# COMMUNICATION.net
KiCad netlist of a schematic drawn in Altium Designer
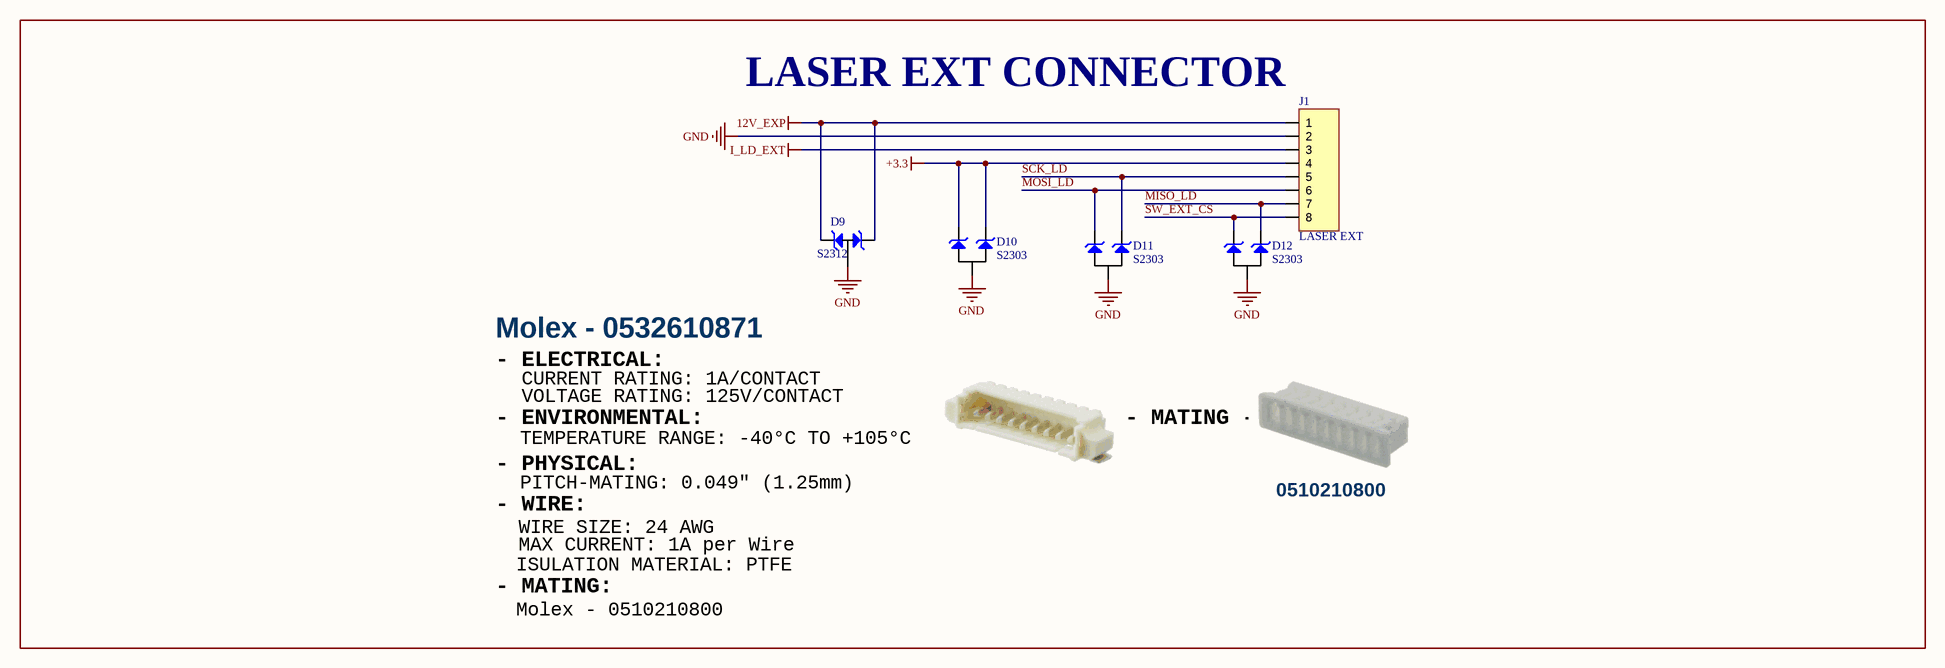
[diagram p0: COMMUNICATION.SchDoc]

(export (version "E")
  (design (tool "Eeschema 10.0.6"))
  (components
    (comp (ref "D9")
      (value "S2312")
      (footprint "SOT23-123")
      (description "TVS DIODE 12VWM 19VC SOT23, P/N:  S2312")
      (libsource (lib "Library") (part "S2315"))
    )
    (comp (ref "D10")
      (value "S2303")
      (footprint "SOT23-123")
      (description "TVS DIODE 3.3VWM 8VC SOT23, P/N:  \r\nS2303")
      (libsource (lib "Library") (part "S2303"))
    )
    (comp (ref "D11")
      (value "S2303")
      (footprint "SOT23-123")
      (description "TVS DIODE 3.3VWM 8VC SOT23, P/N:  \r\nS2303")
      (libsource (lib "Library") (part "S2303"))
    )
    (comp (ref "D12")
      (value "S2303")
      (footprint "SOT23-123")
      (description "TVS DIODE 3.3VWM 8VC SOT23, P/N:  \r\nS2303")
      (libsource (lib "Library") (part "S2303"))
    )
    (comp (ref "J1")
      (value "LASER EXT")
      (footprint "0532610871")
      (description "WR-PHD 2.54 mm Angled Socket Header")
      (fields
        (field (name "MANUFACTURER") "Würth Elektronik eiSos GmbH")
        (field (name "PARTNO") "613008143121")
        (field (name "CREATED BY") "Karrer Zheng")
      )
      (libsource (lib "Library_HUNG") (part "JP8"))
    )
  )
  (nets
    (net (code "1") (name "+3.3") (class "Default")
      (node (ref "D10") (pin "1") (pintype "passive"))
      (node (ref "D10") (pin "3") (pintype "passive"))
      (node (ref "J1") (pin "4") (pinfunction "4_4") (pintype "passive"))
    )
    (net (code "2") (name "/MISO_LD") (class "Default")
      (node (ref "D12") (pin "3") (pintype "passive"))
      (node (ref "J1") (pin "7") (pinfunction "7_7") (pintype "passive"))
    )
    (net (code "3") (name "/MOSI_LD") (class "Default")
      (node (ref "D11") (pin "1") (pintype "passive"))
      (node (ref "J1") (pin "6") (pinfunction "6_6") (pintype "passive"))
    )
    (net (code "4") (name "/SCK_LD") (class "Default")
      (node (ref "D11") (pin "3") (pintype "passive"))
      (node (ref "J1") (pin "5") (pinfunction "5_5") (pintype "passive"))
    )
    (net (code "5") (name "/SW_EXT_CS") (class "Default")
      (node (ref "D12") (pin "1") (pintype "passive"))
      (node (ref "J1") (pin "8") (pinfunction "8_8") (pintype "passive"))
    )
    (net (code "6") (name "12V_EXP") (class "Default")
      (node (ref "D9") (pin "1") (pintype "passive"))
      (node (ref "D9") (pin "3") (pintype "passive"))
      (node (ref "J1") (pin "1") (pinfunction "1_1") (pintype "passive"))
    )
    (net (code "7") (name "GND") (class "Default")
      (node (ref "D10") (pin "2") (pintype "passive"))
      (node (ref "D11") (pin "2") (pintype "passive"))
      (node (ref "D12") (pin "2") (pintype "passive"))
      (node (ref "D9") (pin "2") (pintype "passive"))
      (node (ref "J1") (pin "2") (pinfunction "2_2") (pintype "passive"))
    )
    (net (code "8") (name "I_LD_EXT") (class "Default")
      (node (ref "J1") (pin "3") (pinfunction "3_3") (pintype "passive"))
    )
  )
)
